# pmu.net
KiCad netlist of a schematic drawn in EAGLE
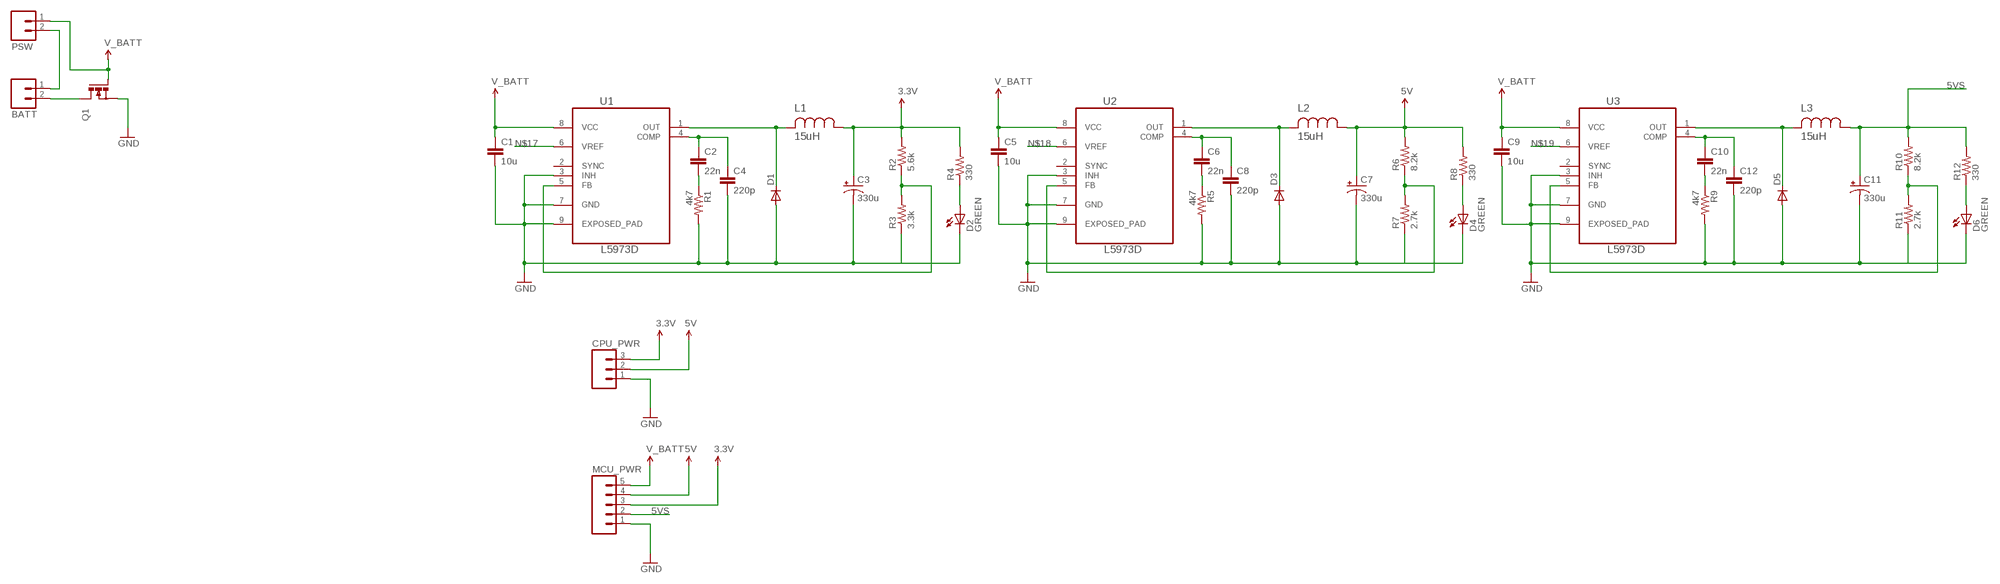
[diagram p0: schematic, sheet 1]

(export (version "E")
  (design (tool "Eeschema 10.0.6"))
  (components
    (comp (ref "BATT")
      (value "M02PTH")
      (footprint "eagle-import:1X02")
      (libsource (lib "eagle-import") (part "M02PTH"))
    )
    (comp (ref "C1")
      (value "10u")
      (footprint "eagle-import:1210")
      (libsource (lib "eagle-import") (part "CAP1210"))
    )
    (comp (ref "C2")
      (value "22n")
      (footprint "eagle-import:0805")
      (libsource (lib "eagle-import") (part "CAP0805"))
    )
    (comp (ref "C3")
      (value "330u")
      (footprint "eagle-import:PANASONIC_E")
      (libsource (lib "eagle-import") (part "CPOL-USE"))
    )
    (comp (ref "C4")
      (value "220p")
      (footprint "eagle-import:0805")
      (libsource (lib "eagle-import") (part "CAP0805"))
    )
    (comp (ref "C5")
      (value "10u")
      (footprint "eagle-import:1210")
      (libsource (lib "eagle-import") (part "CAP1210"))
    )
    (comp (ref "C6")
      (value "22n")
      (footprint "eagle-import:0805")
      (libsource (lib "eagle-import") (part "CAP0805"))
    )
    (comp (ref "C7")
      (value "330u")
      (footprint "eagle-import:PANASONIC_E")
      (libsource (lib "eagle-import") (part "CPOL-USE"))
    )
    (comp (ref "C8")
      (value "220p")
      (footprint "eagle-import:0805")
      (libsource (lib "eagle-import") (part "CAP0805"))
    )
    (comp (ref "C9")
      (value "10u")
      (footprint "eagle-import:1210")
      (libsource (lib "eagle-import") (part "CAP1210"))
    )
    (comp (ref "C10")
      (value "22n")
      (footprint "eagle-import:0805")
      (libsource (lib "eagle-import") (part "CAP0805"))
    )
    (comp (ref "C11")
      (value "330u")
      (footprint "eagle-import:PANASONIC_E")
      (libsource (lib "eagle-import") (part "CPOL-USE"))
    )
    (comp (ref "C12")
      (value "220p")
      (footprint "eagle-import:0805")
      (libsource (lib "eagle-import") (part "CAP0805"))
    )
    (comp (ref "CPU_PWR")
      (value "M03PTH")
      (footprint "eagle-import:1X03")
      (libsource (lib "eagle-import") (part "M03PTH"))
    )
    (comp (ref "D1")
      (value "DIODESMB")
      (footprint "eagle-import:SMB-DIODE")
      (libsource (lib "eagle-import") (part "DIODESMB"))
    )
    (comp (ref "D2")
      (value "GREEN")
      (footprint "eagle-import:LED-1206")
      (libsource (lib "eagle-import") (part "LED-GREENLARGE"))
    )
    (comp (ref "D3")
      (value "DIODESMB")
      (footprint "eagle-import:SMB-DIODE")
      (libsource (lib "eagle-import") (part "DIODESMB"))
    )
    (comp (ref "D4")
      (value "GREEN")
      (footprint "eagle-import:LED-1206")
      (libsource (lib "eagle-import") (part "LED-GREENLARGE"))
    )
    (comp (ref "D5")
      (value "DIODESMB")
      (footprint "eagle-import:SMB-DIODE")
      (libsource (lib "eagle-import") (part "DIODESMB"))
    )
    (comp (ref "D6")
      (value "GREEN")
      (footprint "eagle-import:LED-1206")
      (libsource (lib "eagle-import") (part "LED-GREENLARGE"))
    )
    (comp (ref "L1")
      (value "15uH")
      (footprint "eagle-import:IND_ELL8TP")
      (fields (field (name "MPN") "ELL8TP150MB"))
      (libsource (lib "eagle-import") (part "ELL-8TP8TP150MB"))
    )
    (comp (ref "L2")
      (value "15uH")
      (footprint "eagle-import:IND_ELL8TP")
      (fields (field (name "MPN") "ELL8TP150MB"))
      (libsource (lib "eagle-import") (part "ELL-8TP8TP150MB"))
    )
    (comp (ref "L3")
      (value "15uH")
      (footprint "eagle-import:IND_ELL8TP")
      (fields (field (name "MPN") "ELL8TP150MB"))
      (libsource (lib "eagle-import") (part "ELL-8TP8TP150MB"))
    )
    (comp (ref "MCU_PWR")
      (value "M05PTH")
      (footprint "eagle-import:1X05")
      (libsource (lib "eagle-import") (part "M05PTH"))
    )
    (comp (ref "PSW")
      (value "M02PTH")
      (footprint "eagle-import:1X02")
      (libsource (lib "eagle-import") (part "M02PTH"))
    )
    (comp (ref "Q1")
      (value "N-MOSFET-SO8S")
      (footprint "eagle-import:SO-08")
      (libsource (lib "eagle-import") (part "N-MOSFET-SO8S"))
    )
    (comp (ref "R1")
      (value "4k7")
      (footprint "eagle-import:0805")
      (libsource (lib "eagle-import") (part "RESISTOR0805-RES"))
    )
    (comp (ref "R2")
      (value "5.6k")
      (footprint "eagle-import:0805")
      (libsource (lib "eagle-import") (part "RESISTOR0805-RES"))
    )
    (comp (ref "R3")
      (value "3.3k")
      (footprint "eagle-import:0805")
      (libsource (lib "eagle-import") (part "RESISTOR0805-RES"))
    )
    (comp (ref "R4")
      (value "330")
      (footprint "eagle-import:0805")
      (libsource (lib "eagle-import") (part "RESISTOR0805-RES"))
    )
    (comp (ref "R5")
      (value "4k7")
      (footprint "eagle-import:0805")
      (libsource (lib "eagle-import") (part "RESISTOR0805-RES"))
    )
    (comp (ref "R6")
      (value "8.2k")
      (footprint "eagle-import:0805")
      (libsource (lib "eagle-import") (part "RESISTOR0805-RES"))
    )
    (comp (ref "R7")
      (value "2.7k")
      (footprint "eagle-import:0805")
      (libsource (lib "eagle-import") (part "RESISTOR0805-RES"))
    )
    (comp (ref "R8")
      (value "330")
      (footprint "eagle-import:0805")
      (libsource (lib "eagle-import") (part "RESISTOR0805-RES"))
    )
    (comp (ref "R9")
      (value "4k7")
      (footprint "eagle-import:0805")
      (libsource (lib "eagle-import") (part "RESISTOR0805-RES"))
    )
    (comp (ref "R10")
      (value "8.2k")
      (footprint "eagle-import:0805")
      (libsource (lib "eagle-import") (part "RESISTOR0805-RES"))
    )
    (comp (ref "R11")
      (value "2.7k")
      (footprint "eagle-import:0805")
      (libsource (lib "eagle-import") (part "RESISTOR0805-RES"))
    )
    (comp (ref "R12")
      (value "330")
      (footprint "eagle-import:0805")
      (libsource (lib "eagle-import") (part "RESISTOR0805-RES"))
    )
    (comp (ref "U1")
      (value "L5973D")
      (footprint "eagle-import:SOP127P600X170-9N")
      (libsource (lib "eagle-import") (part "L5973D"))
    )
    (comp (ref "U2")
      (value "L5973D")
      (footprint "eagle-import:SOP127P600X170-9N")
      (libsource (lib "eagle-import") (part "L5973D"))
    )
    (comp (ref "U3")
      (value "L5973D")
      (footprint "eagle-import:SOP127P600X170-9N")
      (libsource (lib "eagle-import") (part "L5973D"))
    )
  )
  (nets
    (net (code "1") (name "/5VS") (class "Default")
      (node (ref "C11") (pin "+") (pinfunction "+_+") (pintype "passive"))
      (node (ref "L3") (pin "1") (pinfunction "1_1") (pintype "passive"))
      (node (ref "MCU_PWR") (pin "2") (pinfunction "2_2") (pintype "passive"))
      (node (ref "R10") (pin "2") (pinfunction "2_2") (pintype "passive"))
      (node (ref "R12") (pin "2") (pinfunction "2_2") (pintype "passive"))
    )
    (net (code "2") (name "/N$17") (class "Default")
      (node (ref "U1") (pin "6") (pinfunction "VREF_6") (pintype "power_in"))
    )
    (net (code "3") (name "/N$18") (class "Default")
      (node (ref "U2") (pin "6") (pinfunction "VREF_6") (pintype "power_in"))
    )
    (net (code "4") (name "/N$19") (class "Default")
      (node (ref "U3") (pin "6") (pinfunction "VREF_6") (pintype "power_in"))
    )
    (net (code "5") (name "3.3V") (class "Default")
      (node (ref "C3") (pin "+") (pinfunction "+_+") (pintype "passive"))
      (node (ref "CPU_PWR") (pin "3") (pinfunction "3_3") (pintype "passive"))
      (node (ref "L1") (pin "1") (pinfunction "1_1") (pintype "passive"))
      (node (ref "MCU_PWR") (pin "3") (pinfunction "3_3") (pintype "passive"))
      (node (ref "R2") (pin "2") (pinfunction "2_2") (pintype "passive"))
      (node (ref "R4") (pin "2") (pinfunction "2_2") (pintype "passive"))
    )
    (net (code "6") (name "5V") (class "Default")
      (node (ref "C7") (pin "+") (pinfunction "+_+") (pintype "passive"))
      (node (ref "CPU_PWR") (pin "2") (pinfunction "2_2") (pintype "passive"))
      (node (ref "L2") (pin "1") (pinfunction "1_1") (pintype "passive"))
      (node (ref "MCU_PWR") (pin "4") (pinfunction "4_4") (pintype "passive"))
      (node (ref "R6") (pin "2") (pinfunction "2_2") (pintype "passive"))
      (node (ref "R8") (pin "2") (pinfunction "2_2") (pintype "passive"))
    )
    (net (code "7") (name "GND") (class "Default")
      (node (ref "C1") (pin "2") (pinfunction "2_2") (pintype "passive"))
      (node (ref "C11") (pin "-") (pinfunction "-_-") (pintype "passive"))
      (node (ref "C12") (pin "2") (pinfunction "2_2") (pintype "passive"))
      (node (ref "C3") (pin "-") (pinfunction "-_-") (pintype "passive"))
      (node (ref "C4") (pin "2") (pinfunction "2_2") (pintype "passive"))
      (node (ref "C5") (pin "2") (pinfunction "2_2") (pintype "passive"))
      (node (ref "C7") (pin "-") (pinfunction "-_-") (pintype "passive"))
      (node (ref "C8") (pin "2") (pinfunction "2_2") (pintype "passive"))
      (node (ref "C9") (pin "2") (pinfunction "2_2") (pintype "passive"))
      (node (ref "CPU_PWR") (pin "1") (pinfunction "1_1") (pintype "passive"))
      (node (ref "D1") (pin "A") (pinfunction "A_A") (pintype "passive"))
      (node (ref "D2") (pin "C") (pinfunction "C_C") (pintype "passive"))
      (node (ref "D3") (pin "A") (pinfunction "A_A") (pintype "passive"))
      (node (ref "D4") (pin "C") (pinfunction "C_C") (pintype "passive"))
      (node (ref "D5") (pin "A") (pinfunction "A_A") (pintype "passive"))
      (node (ref "D6") (pin "C") (pinfunction "C_C") (pintype "passive"))
      (node (ref "MCU_PWR") (pin "1") (pinfunction "1_1") (pintype "passive"))
      (node (ref "Q1") (pin "1") (pinfunction "S_1") (pintype "passive"))
      (node (ref "Q1") (pin "2") (pinfunction "S_2") (pintype "passive"))
      (node (ref "Q1") (pin "3") (pinfunction "S_3") (pintype "passive"))
      (node (ref "R1") (pin "2") (pinfunction "2_2") (pintype "passive"))
      (node (ref "R11") (pin "1") (pinfunction "1_1") (pintype "passive"))
      (node (ref "R3") (pin "1") (pinfunction "1_1") (pintype "passive"))
      (node (ref "R5") (pin "2") (pinfunction "2_2") (pintype "passive"))
      (node (ref "R7") (pin "1") (pinfunction "1_1") (pintype "passive"))
      (node (ref "R9") (pin "2") (pinfunction "2_2") (pintype "passive"))
      (node (ref "U1") (pin "3") (pinfunction "INH_3") (pintype "input"))
      (node (ref "U1") (pin "7") (pinfunction "GND_7") (pintype "passive"))
      (node (ref "U1") (pin "9") (pinfunction "EXPOSED_PAD_9") (pintype "passive"))
      (node (ref "U2") (pin "3") (pinfunction "INH_3") (pintype "input"))
      (node (ref "U2") (pin "7") (pinfunction "GND_7") (pintype "passive"))
      (node (ref "U2") (pin "9") (pinfunction "EXPOSED_PAD_9") (pintype "passive"))
      (node (ref "U3") (pin "3") (pinfunction "INH_3") (pintype "input"))
      (node (ref "U3") (pin "7") (pinfunction "GND_7") (pintype "passive"))
      (node (ref "U3") (pin "9") (pinfunction "EXPOSED_PAD_9") (pintype "passive"))
    )
    (net (code "8") (name "Net-(BATT-Pad1)") (class "Default")
      (node (ref "BATT") (pin "1") (pinfunction "1_1") (pintype "passive"))
      (node (ref "PSW") (pin "2") (pinfunction "2_2") (pintype "passive"))
    )
    (net (code "9") (name "Net-(BATT-Pad2)") (class "Default")
      (node (ref "BATT") (pin "2") (pinfunction "2_2") (pintype "passive"))
      (node (ref "Q1") (pin "5") (pinfunction "D_5") (pintype "passive"))
      (node (ref "Q1") (pin "6") (pinfunction "D_6") (pintype "passive"))
      (node (ref "Q1") (pin "7") (pinfunction "D_7") (pintype "passive"))
      (node (ref "Q1") (pin "8") (pinfunction "D_8") (pintype "passive"))
    )
    (net (code "10") (name "Net-(C2-Pad2)") (class "Default")
      (node (ref "C2") (pin "2") (pinfunction "2_2") (pintype "passive"))
      (node (ref "R1") (pin "1") (pinfunction "1_1") (pintype "passive"))
    )
    (net (code "11") (name "Net-(C6-Pad2)") (class "Default")
      (node (ref "C6") (pin "2") (pinfunction "2_2") (pintype "passive"))
      (node (ref "R5") (pin "1") (pinfunction "1_1") (pintype "passive"))
    )
    (net (code "12") (name "Net-(C10-Pad2)") (class "Default")
      (node (ref "C10") (pin "2") (pinfunction "2_2") (pintype "passive"))
      (node (ref "R9") (pin "1") (pinfunction "1_1") (pintype "passive"))
    )
    (net (code "13") (name "Net-(D2-PadA)") (class "Default")
      (node (ref "D2") (pin "A") (pinfunction "A_A") (pintype "passive"))
      (node (ref "R4") (pin "1") (pinfunction "1_1") (pintype "passive"))
    )
    (net (code "14") (name "Net-(D4-PadA)") (class "Default")
      (node (ref "D4") (pin "A") (pinfunction "A_A") (pintype "passive"))
      (node (ref "R8") (pin "1") (pinfunction "1_1") (pintype "passive"))
    )
    (net (code "15") (name "Net-(D6-PadA)") (class "Default")
      (node (ref "D6") (pin "A") (pinfunction "A_A") (pintype "passive"))
      (node (ref "R12") (pin "1") (pinfunction "1_1") (pintype "passive"))
    )
    (net (code "16") (name "Net-(U1-COMP)") (class "Default")
      (node (ref "C2") (pin "1") (pinfunction "1_1") (pintype "passive"))
      (node (ref "C4") (pin "1") (pinfunction "1_1") (pintype "passive"))
      (node (ref "U1") (pin "4") (pinfunction "COMP_4") (pintype "output"))
    )
    (net (code "17") (name "Net-(U1-FB)") (class "Default")
      (node (ref "R2") (pin "1") (pinfunction "1_1") (pintype "passive"))
      (node (ref "R3") (pin "2") (pinfunction "2_2") (pintype "passive"))
      (node (ref "U1") (pin "5") (pinfunction "FB_5") (pintype "input"))
    )
    (net (code "18") (name "Net-(U1-OUT)") (class "Default")
      (node (ref "D1") (pin "C") (pinfunction "C_C") (pintype "passive"))
      (node (ref "L1") (pin "2") (pinfunction "2_2") (pintype "passive"))
      (node (ref "U1") (pin "1") (pinfunction "OUT_1") (pintype "output"))
    )
    (net (code "19") (name "Net-(U2-COMP)") (class "Default")
      (node (ref "C6") (pin "1") (pinfunction "1_1") (pintype "passive"))
      (node (ref "C8") (pin "1") (pinfunction "1_1") (pintype "passive"))
      (node (ref "U2") (pin "4") (pinfunction "COMP_4") (pintype "output"))
    )
    (net (code "20") (name "Net-(U2-FB)") (class "Default")
      (node (ref "R6") (pin "1") (pinfunction "1_1") (pintype "passive"))
      (node (ref "R7") (pin "2") (pinfunction "2_2") (pintype "passive"))
      (node (ref "U2") (pin "5") (pinfunction "FB_5") (pintype "input"))
    )
    (net (code "21") (name "Net-(U2-OUT)") (class "Default")
      (node (ref "D3") (pin "C") (pinfunction "C_C") (pintype "passive"))
      (node (ref "L2") (pin "2") (pinfunction "2_2") (pintype "passive"))
      (node (ref "U2") (pin "1") (pinfunction "OUT_1") (pintype "output"))
    )
    (net (code "22") (name "Net-(U3-COMP)") (class "Default")
      (node (ref "C10") (pin "1") (pinfunction "1_1") (pintype "passive"))
      (node (ref "C12") (pin "1") (pinfunction "1_1") (pintype "passive"))
      (node (ref "U3") (pin "4") (pinfunction "COMP_4") (pintype "output"))
    )
    (net (code "23") (name "Net-(U3-FB)") (class "Default")
      (node (ref "R10") (pin "1") (pinfunction "1_1") (pintype "passive"))
      (node (ref "R11") (pin "2") (pinfunction "2_2") (pintype "passive"))
      (node (ref "U3") (pin "5") (pinfunction "FB_5") (pintype "input"))
    )
    (net (code "24") (name "Net-(U3-OUT)") (class "Default")
      (node (ref "D5") (pin "C") (pinfunction "C_C") (pintype "passive"))
      (node (ref "L3") (pin "2") (pinfunction "2_2") (pintype "passive"))
      (node (ref "U3") (pin "1") (pinfunction "OUT_1") (pintype "output"))
    )
    (net (code "25") (name "V_BATT") (class "Default")
      (node (ref "C1") (pin "1") (pinfunction "1_1") (pintype "passive"))
      (node (ref "C5") (pin "1") (pinfunction "1_1") (pintype "passive"))
      (node (ref "C9") (pin "1") (pinfunction "1_1") (pintype "passive"))
      (node (ref "MCU_PWR") (pin "5") (pinfunction "5_5") (pintype "passive"))
      (node (ref "PSW") (pin "1") (pinfunction "1_1") (pintype "passive"))
      (node (ref "Q1") (pin "4") (pinfunction "G_4") (pintype "passive"))
      (node (ref "U1") (pin "8") (pinfunction "VCC_8") (pintype "power_in"))
      (node (ref "U2") (pin "8") (pinfunction "VCC_8") (pintype "power_in"))
      (node (ref "U3") (pin "8") (pinfunction "VCC_8") (pintype "power_in"))
    )
    (net (code "26") (name "unconnected-(U1-SYNC-Pad2)") (class "Default")
      (node (ref "U1") (pin "2") (pinfunction "SYNC_2") (pintype "input"))
    )
    (net (code "27") (name "unconnected-(U2-SYNC-Pad2)") (class "Default")
      (node (ref "U2") (pin "2") (pinfunction "SYNC_2") (pintype "input"))
    )
    (net (code "28") (name "unconnected-(U3-SYNC-Pad2)") (class "Default")
      (node (ref "U3") (pin "2") (pinfunction "SYNC_2") (pintype "input"))
    )
  )
)
